# RGB_32x64_Shield_for_Arduino_Mega.net
KiCad netlist of a schematic drawn in EAGLE
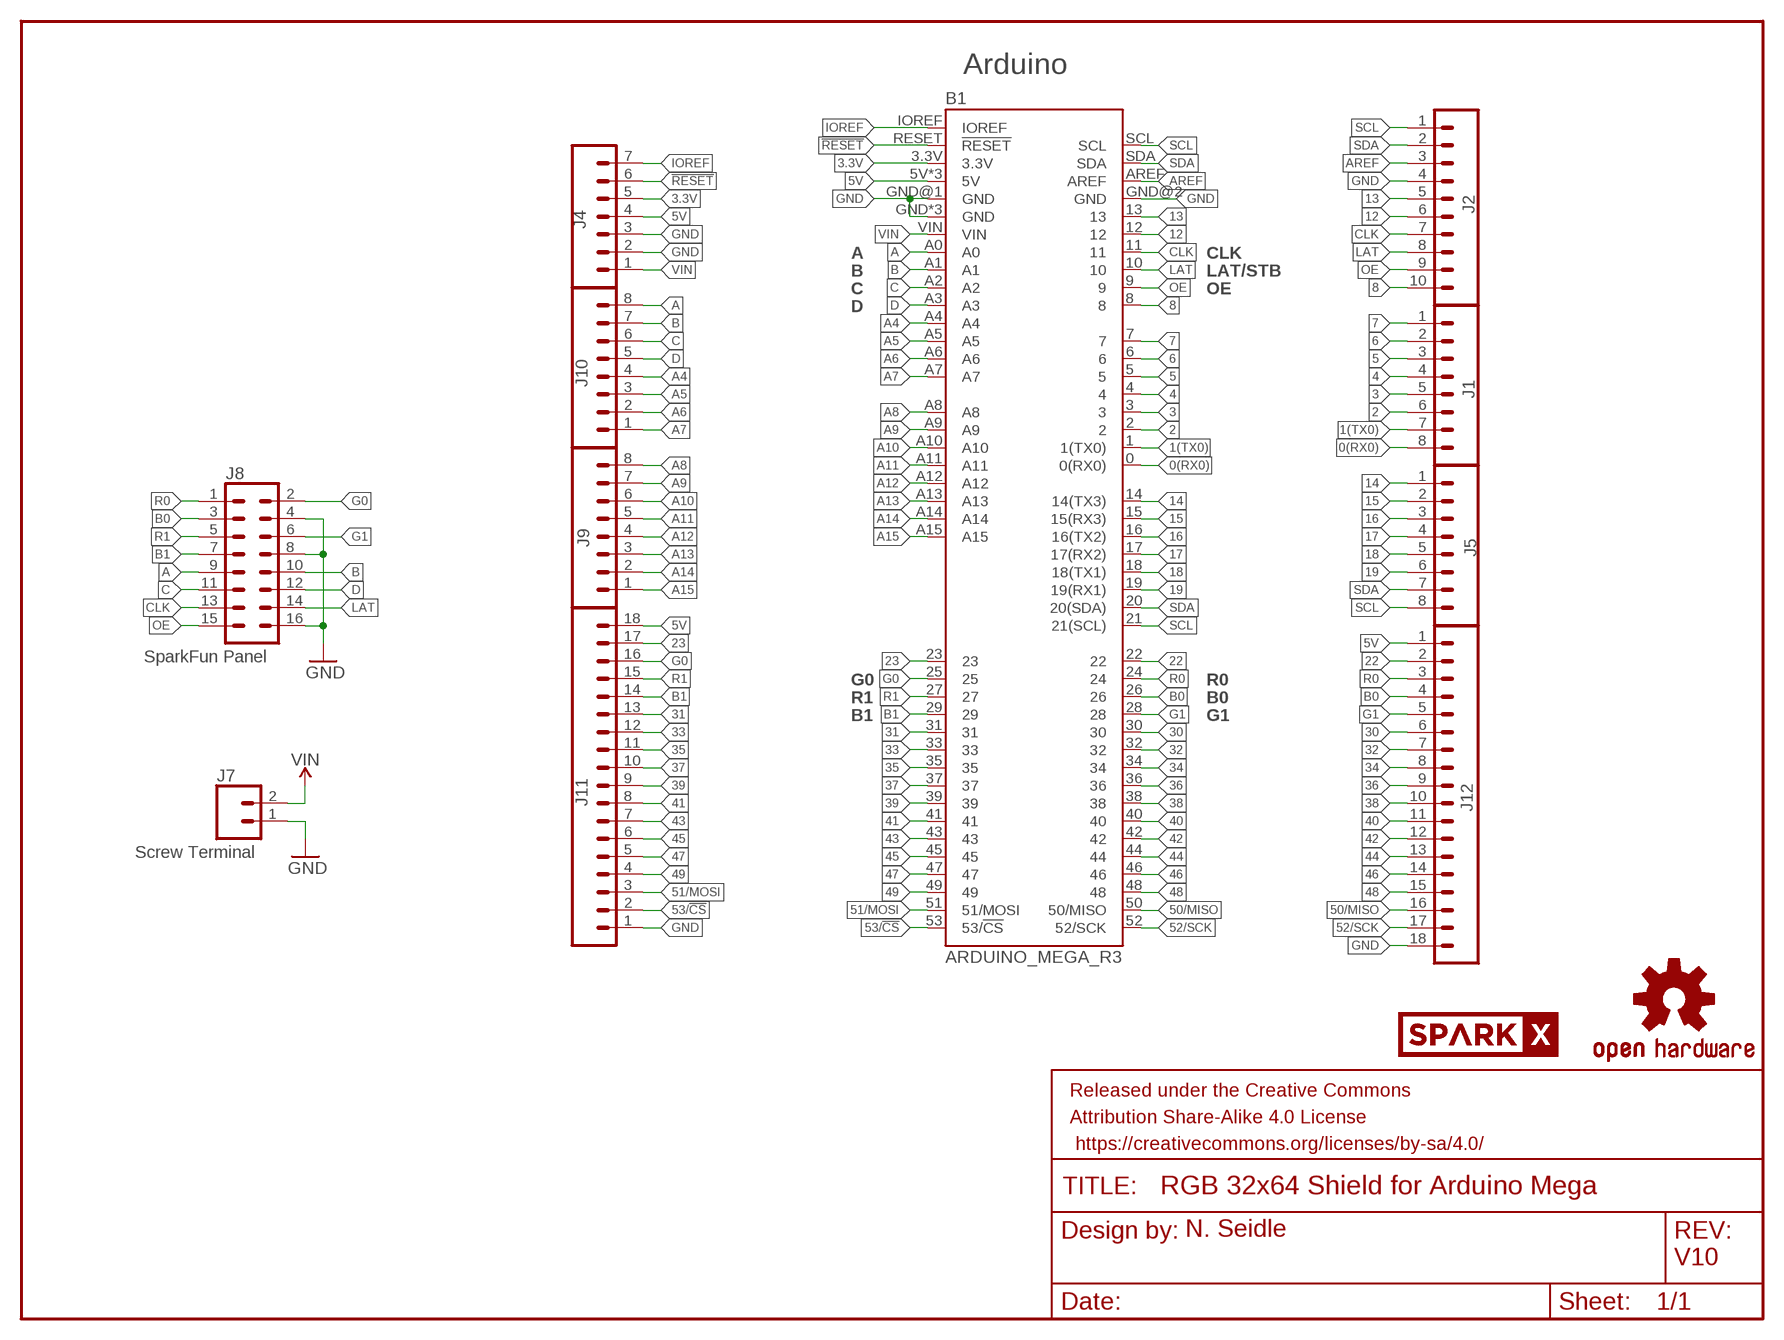
[diagram p0: schematic, sheet 1]

(export (version "E")
  (design (tool "Eeschema 10.0.6"))
  (components
    (comp (ref "B1")
      (value "ARDUINO_MEGA_R3")
      (footprint "eagle-import:ARDUINO_MEGA_NO_SILK")
      (libsource (lib "eagle-import") (part "ARDUINO_MEGA_R3FULL"))
    )
    (comp (ref "FRAME1")
      (value "FRAME-LETTER")
      (footprint "eagle-import:CREATIVE_COMMONS")
      (libsource (lib "eagle-import") (part "FRAME-LETTER"))
    )
    (comp (ref "J1")
      (value "CONN_08NO_SILK_FEMALE_PTH")
      (footprint "eagle-import:1X08_NO_SILK")
      (libsource (lib "eagle-import") (part "CONN_08NO_SILK_FEMALE_PTH"))
    )
    (comp (ref "J2")
      (value "CONN_10NO_SILK_PTH_FEMALE")
      (footprint "eagle-import:1X10_NO_SILK")
      (libsource (lib "eagle-import") (part "CONN_10NO_SILK_PTH_FEMALE"))
    )
    (comp (ref "J4")
      (value "CONN_07NO_SILK")
      (footprint "eagle-import:1X07_NO_SILK")
      (libsource (lib "eagle-import") (part "CONN_07NO_SILK"))
    )
    (comp (ref "J5")
      (value "CONN_08NO_SILK_FEMALE_PTH")
      (footprint "eagle-import:1X08_NO_SILK")
      (libsource (lib "eagle-import") (part "CONN_08NO_SILK_FEMALE_PTH"))
    )
    (comp (ref "J7")
      (value "Screw Terminal")
      (footprint "eagle-import:SCREWTERMINAL-5MM-2")
      (libsource (lib "eagle-import") (part "CONN_025MM"))
    )
    (comp (ref "J8")
      (value "SparkFun Panel")
      (footprint "eagle-import:2X8-SHROUDED_LOCK")
      (libsource (lib "eagle-import") (part "CONN_08X2_SHROUD"))
    )
    (comp (ref "J9")
      (value "CONN_08NO_SILK_FEMALE_PTH")
      (footprint "eagle-import:1X08_NO_SILK")
      (libsource (lib "eagle-import") (part "CONN_08NO_SILK_FEMALE_PTH"))
    )
    (comp (ref "J10")
      (value "CONN_08NO_SILK_FEMALE_PTH")
      (footprint "eagle-import:1X08_NO_SILK")
      (libsource (lib "eagle-import") (part "CONN_08NO_SILK_FEMALE_PTH"))
    )
    (comp (ref "J11")
      (value "CONN_18")
      (footprint "eagle-import:1X18_NO_SILK")
      (libsource (lib "eagle-import") (part "CONN_18"))
    )
    (comp (ref "J12")
      (value "CONN_18")
      (footprint "eagle-import:1X18_NO_SILK")
      (libsource (lib "eagle-import") (part "CONN_18"))
    )
    (comp (ref "LOGO1")
      (value "OSHW-LOGOMINI")
      (footprint "eagle-import:OSHW-LOGO-MINI")
      (libsource (lib "eagle-import") (part "OSHW-LOGOMINI"))
    )
    (comp (ref "U$91")
      (value "SPARKX-LOGO4")
      (footprint "eagle-import:SPARKX-MEDIUM")
      (libsource (lib "eagle-import") (part "SPARKX-LOGO4"))
    )
  )
  (nets
    (net (code "1") (name "/53{slash}~{CS}") (class "Default")
      (node (ref "B1") (pin "53") (pinfunction "53/~{CS}_53") (pintype "bidirectional"))
      (node (ref "J11") (pin "2") (pinfunction "2_2") (pintype "passive"))
    )
    (net (code "2") (name "/~{RESET}") (class "Default")
      (node (ref "B1") (pin "RESET") (pinfunction "~{RESET}_RESET") (pintype "bidirectional"))
      (node (ref "J4") (pin "6") (pinfunction "6_6") (pintype "passive"))
    )
    (net (code "3") (name "0(RX0)") (class "Default")
      (node (ref "B1") (pin "0") (pinfunction "0(RX0)_0") (pintype "bidirectional"))
      (node (ref "J1") (pin "8") (pinfunction "8_8") (pintype "passive"))
    )
    (net (code "4") (name "1(TX0)") (class "Default")
      (node (ref "B1") (pin "1") (pinfunction "1(TX0)_1") (pintype "bidirectional"))
      (node (ref "J1") (pin "7") (pinfunction "7_7") (pintype "passive"))
    )
    (net (code "5") (name "2") (class "Default")
      (node (ref "B1") (pin "2") (pinfunction "2_2") (pintype "bidirectional"))
      (node (ref "J1") (pin "6") (pinfunction "6_6") (pintype "passive"))
    )
    (net (code "6") (name "3") (class "Default")
      (node (ref "B1") (pin "3") (pinfunction "3_3") (pintype "bidirectional"))
      (node (ref "J1") (pin "5") (pinfunction "5_5") (pintype "passive"))
    )
    (net (code "7") (name "3.3V") (class "Default")
      (node (ref "B1") (pin "3.3V") (pinfunction "3.3V_3.3V") (pintype "bidirectional"))
      (node (ref "J4") (pin "5") (pinfunction "5_5") (pintype "passive"))
    )
    (net (code "8") (name "4") (class "Default")
      (node (ref "B1") (pin "4") (pinfunction "4_4") (pintype "bidirectional"))
      (node (ref "J1") (pin "4") (pinfunction "4_4") (pintype "passive"))
    )
    (net (code "9") (name "5") (class "Default")
      (node (ref "B1") (pin "5") (pinfunction "5_5") (pintype "bidirectional"))
      (node (ref "J1") (pin "3") (pinfunction "3_3") (pintype "passive"))
    )
    (net (code "10") (name "5V") (class "Default")
      (node (ref "B1") (pin "5V") (pinfunction "5V_5V") (pintype "bidirectional"))
      (node (ref "B1") (pin "5V@1") (pinfunction "5V_5V@1") (pintype "bidirectional"))
      (node (ref "B1") (pin "5V@2") (pinfunction "5V_5V@2") (pintype "bidirectional"))
      (node (ref "J11") (pin "18") (pinfunction "18_18") (pintype "passive"))
      (node (ref "J12") (pin "1") (pinfunction "1_1") (pintype "passive"))
      (node (ref "J4") (pin "4") (pinfunction "4_4") (pintype "passive"))
    )
    (net (code "11") (name "6") (class "Default")
      (node (ref "B1") (pin "6") (pinfunction "6_6") (pintype "bidirectional"))
      (node (ref "J1") (pin "2") (pinfunction "2_2") (pintype "passive"))
    )
    (net (code "12") (name "7") (class "Default")
      (node (ref "B1") (pin "7") (pinfunction "7_7") (pintype "bidirectional"))
      (node (ref "J1") (pin "1") (pinfunction "1_1") (pintype "passive"))
    )
    (net (code "13") (name "8") (class "Default")
      (node (ref "B1") (pin "8") (pinfunction "8_8") (pintype "bidirectional"))
      (node (ref "J2") (pin "10") (pinfunction "10_10") (pintype "passive"))
    )
    (net (code "14") (name "12") (class "Default")
      (node (ref "B1") (pin "12") (pinfunction "12_12") (pintype "bidirectional"))
      (node (ref "J2") (pin "6") (pinfunction "6_6") (pintype "passive"))
    )
    (net (code "15") (name "13") (class "Default")
      (node (ref "B1") (pin "13") (pinfunction "13_13") (pintype "bidirectional"))
      (node (ref "J2") (pin "5") (pinfunction "5_5") (pintype "passive"))
    )
    (net (code "16") (name "14") (class "Default")
      (node (ref "B1") (pin "14") (pinfunction "14(TX3)_14") (pintype "bidirectional"))
      (node (ref "J5") (pin "1") (pinfunction "1_1") (pintype "passive"))
    )
    (net (code "17") (name "15") (class "Default")
      (node (ref "B1") (pin "15") (pinfunction "15(RX3)_15") (pintype "bidirectional"))
      (node (ref "J5") (pin "2") (pinfunction "2_2") (pintype "passive"))
    )
    (net (code "18") (name "16") (class "Default")
      (node (ref "B1") (pin "16") (pinfunction "16(TX2)_16") (pintype "bidirectional"))
      (node (ref "J5") (pin "3") (pinfunction "3_3") (pintype "passive"))
    )
    (net (code "19") (name "17") (class "Default")
      (node (ref "B1") (pin "17") (pinfunction "17(RX2)_17") (pintype "bidirectional"))
      (node (ref "J5") (pin "4") (pinfunction "4_4") (pintype "passive"))
    )
    (net (code "20") (name "18") (class "Default")
      (node (ref "B1") (pin "18") (pinfunction "18(TX1)_18") (pintype "bidirectional"))
      (node (ref "J5") (pin "5") (pinfunction "5_5") (pintype "passive"))
    )
    (net (code "21") (name "19") (class "Default")
      (node (ref "B1") (pin "19") (pinfunction "19(RX1)_19") (pintype "bidirectional"))
      (node (ref "J5") (pin "6") (pinfunction "6_6") (pintype "passive"))
    )
    (net (code "22") (name "22") (class "Default")
      (node (ref "B1") (pin "22") (pinfunction "22_22") (pintype "bidirectional"))
      (node (ref "J12") (pin "2") (pinfunction "2_2") (pintype "passive"))
    )
    (net (code "23") (name "23") (class "Default")
      (node (ref "B1") (pin "23") (pinfunction "23_23") (pintype "bidirectional"))
      (node (ref "J11") (pin "17") (pinfunction "17_17") (pintype "passive"))
    )
    (net (code "24") (name "30") (class "Default")
      (node (ref "B1") (pin "30") (pinfunction "30_30") (pintype "bidirectional"))
      (node (ref "J12") (pin "6") (pinfunction "6_6") (pintype "passive"))
    )
    (net (code "25") (name "31") (class "Default")
      (node (ref "B1") (pin "31") (pinfunction "31_31") (pintype "bidirectional"))
      (node (ref "J11") (pin "13") (pinfunction "13_13") (pintype "passive"))
    )
    (net (code "26") (name "32") (class "Default")
      (node (ref "B1") (pin "32") (pinfunction "32_32") (pintype "bidirectional"))
      (node (ref "J12") (pin "7") (pinfunction "7_7") (pintype "passive"))
    )
    (net (code "27") (name "33") (class "Default")
      (node (ref "B1") (pin "33") (pinfunction "33_33") (pintype "bidirectional"))
      (node (ref "J11") (pin "12") (pinfunction "12_12") (pintype "passive"))
    )
    (net (code "28") (name "34") (class "Default")
      (node (ref "B1") (pin "34") (pinfunction "34_34") (pintype "bidirectional"))
      (node (ref "J12") (pin "8") (pinfunction "8_8") (pintype "passive"))
    )
    (net (code "29") (name "35") (class "Default")
      (node (ref "B1") (pin "35") (pinfunction "35_35") (pintype "bidirectional"))
      (node (ref "J11") (pin "11") (pinfunction "11_11") (pintype "passive"))
    )
    (net (code "30") (name "36") (class "Default")
      (node (ref "B1") (pin "36") (pinfunction "36_36") (pintype "bidirectional"))
      (node (ref "J12") (pin "9") (pinfunction "9_9") (pintype "passive"))
    )
    (net (code "31") (name "37") (class "Default")
      (node (ref "B1") (pin "37") (pinfunction "37_37") (pintype "bidirectional"))
      (node (ref "J11") (pin "10") (pinfunction "10_10") (pintype "passive"))
    )
    (net (code "32") (name "38") (class "Default")
      (node (ref "B1") (pin "38") (pinfunction "38_38") (pintype "bidirectional"))
      (node (ref "J12") (pin "10") (pinfunction "10_10") (pintype "passive"))
    )
    (net (code "33") (name "39") (class "Default")
      (node (ref "B1") (pin "39") (pinfunction "39_39") (pintype "bidirectional"))
      (node (ref "J11") (pin "9") (pinfunction "9_9") (pintype "passive"))
    )
    (net (code "34") (name "40") (class "Default")
      (node (ref "B1") (pin "40") (pinfunction "40_40") (pintype "bidirectional"))
      (node (ref "J12") (pin "11") (pinfunction "11_11") (pintype "passive"))
    )
    (net (code "35") (name "41") (class "Default")
      (node (ref "B1") (pin "41") (pinfunction "41_41") (pintype "bidirectional"))
      (node (ref "J11") (pin "8") (pinfunction "8_8") (pintype "passive"))
    )
    (net (code "36") (name "42") (class "Default")
      (node (ref "B1") (pin "42") (pinfunction "42_42") (pintype "bidirectional"))
      (node (ref "J12") (pin "12") (pinfunction "12_12") (pintype "passive"))
    )
    (net (code "37") (name "43") (class "Default")
      (node (ref "B1") (pin "43") (pinfunction "43_43") (pintype "bidirectional"))
      (node (ref "J11") (pin "7") (pinfunction "7_7") (pintype "passive"))
    )
    (net (code "38") (name "44") (class "Default")
      (node (ref "B1") (pin "44") (pinfunction "44_44") (pintype "bidirectional"))
      (node (ref "J12") (pin "13") (pinfunction "13_13") (pintype "passive"))
    )
    (net (code "39") (name "45") (class "Default")
      (node (ref "B1") (pin "45") (pinfunction "45_45") (pintype "bidirectional"))
      (node (ref "J11") (pin "6") (pinfunction "6_6") (pintype "passive"))
    )
    (net (code "40") (name "46") (class "Default")
      (node (ref "B1") (pin "46") (pinfunction "46_46") (pintype "bidirectional"))
      (node (ref "J12") (pin "14") (pinfunction "14_14") (pintype "passive"))
    )
    (net (code "41") (name "47") (class "Default")
      (node (ref "B1") (pin "47") (pinfunction "47_47") (pintype "bidirectional"))
      (node (ref "J11") (pin "5") (pinfunction "5_5") (pintype "passive"))
    )
    (net (code "42") (name "48") (class "Default")
      (node (ref "B1") (pin "48") (pinfunction "48_48") (pintype "bidirectional"))
      (node (ref "J12") (pin "15") (pinfunction "15_15") (pintype "passive"))
    )
    (net (code "43") (name "49") (class "Default")
      (node (ref "B1") (pin "49") (pinfunction "49_49") (pintype "bidirectional"))
      (node (ref "J11") (pin "4") (pinfunction "4_4") (pintype "passive"))
    )
    (net (code "44") (name "50{slash}MISO") (class "Default")
      (node (ref "B1") (pin "50") (pinfunction "50/MISO_50") (pintype "bidirectional"))
      (node (ref "J12") (pin "16") (pinfunction "16_16") (pintype "passive"))
    )
    (net (code "45") (name "51{slash}MOSI") (class "Default")
      (node (ref "B1") (pin "51") (pinfunction "51/MOSI_51") (pintype "bidirectional"))
      (node (ref "J11") (pin "3") (pinfunction "3_3") (pintype "passive"))
    )
    (net (code "46") (name "52{slash}SCK") (class "Default")
      (node (ref "B1") (pin "52") (pinfunction "52/SCK_52") (pintype "bidirectional"))
      (node (ref "J12") (pin "17") (pinfunction "17_17") (pintype "passive"))
    )
    (net (code "47") (name "A") (class "Default")
      (node (ref "B1") (pin "A0") (pinfunction "A0_A0") (pintype "bidirectional"))
      (node (ref "J10") (pin "8") (pinfunction "8_8") (pintype "passive"))
      (node (ref "J8") (pin "9") (pinfunction "9_9") (pintype "passive"))
    )
    (net (code "48") (name "A4") (class "Default")
      (node (ref "B1") (pin "A4") (pinfunction "A4_A4") (pintype "bidirectional"))
      (node (ref "J10") (pin "4") (pinfunction "4_4") (pintype "passive"))
    )
    (net (code "49") (name "A5") (class "Default")
      (node (ref "B1") (pin "A5") (pinfunction "A5_A5") (pintype "bidirectional"))
      (node (ref "J10") (pin "3") (pinfunction "3_3") (pintype "passive"))
    )
    (net (code "50") (name "A6") (class "Default")
      (node (ref "B1") (pin "A6") (pinfunction "A6_A6") (pintype "bidirectional"))
      (node (ref "J10") (pin "2") (pinfunction "2_2") (pintype "passive"))
    )
    (net (code "51") (name "A7") (class "Default")
      (node (ref "B1") (pin "A7") (pinfunction "A7_A7") (pintype "bidirectional"))
      (node (ref "J10") (pin "1") (pinfunction "1_1") (pintype "passive"))
    )
    (net (code "52") (name "A8") (class "Default")
      (node (ref "B1") (pin "A8") (pinfunction "A8_A8") (pintype "bidirectional"))
      (node (ref "J9") (pin "8") (pinfunction "8_8") (pintype "passive"))
    )
    (net (code "53") (name "A9") (class "Default")
      (node (ref "B1") (pin "A9") (pinfunction "A9_A9") (pintype "bidirectional"))
      (node (ref "J9") (pin "7") (pinfunction "7_7") (pintype "passive"))
    )
    (net (code "54") (name "A10") (class "Default")
      (node (ref "B1") (pin "A10") (pinfunction "A10_A10") (pintype "bidirectional"))
      (node (ref "J9") (pin "6") (pinfunction "6_6") (pintype "passive"))
    )
    (net (code "55") (name "A11") (class "Default")
      (node (ref "B1") (pin "A11") (pinfunction "A11_A11") (pintype "bidirectional"))
      (node (ref "J9") (pin "5") (pinfunction "5_5") (pintype "passive"))
    )
    (net (code "56") (name "A12") (class "Default")
      (node (ref "B1") (pin "A12") (pinfunction "A12_A12") (pintype "bidirectional"))
      (node (ref "J9") (pin "4") (pinfunction "4_4") (pintype "passive"))
    )
    (net (code "57") (name "A13") (class "Default")
      (node (ref "B1") (pin "A13") (pinfunction "A13_A13") (pintype "bidirectional"))
      (node (ref "J9") (pin "3") (pinfunction "3_3") (pintype "passive"))
    )
    (net (code "58") (name "A14") (class "Default")
      (node (ref "B1") (pin "A14") (pinfunction "A14_A14") (pintype "bidirectional"))
      (node (ref "J9") (pin "2") (pinfunction "2_2") (pintype "passive"))
    )
    (net (code "59") (name "A15") (class "Default")
      (node (ref "B1") (pin "A15") (pinfunction "A15_A15") (pintype "bidirectional"))
      (node (ref "J9") (pin "1") (pinfunction "1_1") (pintype "passive"))
    )
    (net (code "60") (name "AREF") (class "Default")
      (node (ref "B1") (pin "AREF") (pinfunction "AREF_AREF") (pintype "bidirectional"))
      (node (ref "J2") (pin "3") (pinfunction "3_3") (pintype "passive"))
    )
    (net (code "61") (name "B") (class "Default")
      (node (ref "B1") (pin "A1") (pinfunction "A1_A1") (pintype "bidirectional"))
      (node (ref "J10") (pin "7") (pinfunction "7_7") (pintype "passive"))
      (node (ref "J8") (pin "10") (pinfunction "10_10") (pintype "passive"))
    )
    (net (code "62") (name "B0") (class "Default")
      (node (ref "B1") (pin "26") (pinfunction "26_26") (pintype "bidirectional"))
      (node (ref "J12") (pin "4") (pinfunction "4_4") (pintype "passive"))
      (node (ref "J8") (pin "3") (pinfunction "3_3") (pintype "passive"))
    )
    (net (code "63") (name "B1") (class "Default")
      (node (ref "B1") (pin "29") (pinfunction "29_29") (pintype "bidirectional"))
      (node (ref "J11") (pin "14") (pinfunction "14_14") (pintype "passive"))
      (node (ref "J8") (pin "7") (pinfunction "7_7") (pintype "passive"))
    )
    (net (code "64") (name "C") (class "Default")
      (node (ref "B1") (pin "A2") (pinfunction "A2_A2") (pintype "bidirectional"))
      (node (ref "J10") (pin "6") (pinfunction "6_6") (pintype "passive"))
      (node (ref "J8") (pin "11") (pinfunction "11_11") (pintype "passive"))
    )
    (net (code "65") (name "CLK") (class "Default")
      (node (ref "B1") (pin "11") (pinfunction "11_11") (pintype "bidirectional"))
      (node (ref "J2") (pin "7") (pinfunction "7_7") (pintype "passive"))
      (node (ref "J8") (pin "13") (pinfunction "13_13") (pintype "passive"))
    )
    (net (code "66") (name "D") (class "Default")
      (node (ref "B1") (pin "A3") (pinfunction "A3_A3") (pintype "bidirectional"))
      (node (ref "J10") (pin "5") (pinfunction "5_5") (pintype "passive"))
      (node (ref "J8") (pin "12") (pinfunction "12_12") (pintype "passive"))
    )
    (net (code "67") (name "G0") (class "Default")
      (node (ref "B1") (pin "25") (pinfunction "25_25") (pintype "bidirectional"))
      (node (ref "J11") (pin "16") (pinfunction "16_16") (pintype "passive"))
      (node (ref "J8") (pin "2") (pinfunction "2_2") (pintype "passive"))
    )
    (net (code "68") (name "G1") (class "Default")
      (node (ref "B1") (pin "28") (pinfunction "28_28") (pintype "bidirectional"))
      (node (ref "J12") (pin "5") (pinfunction "5_5") (pintype "passive"))
      (node (ref "J8") (pin "6") (pinfunction "6_6") (pintype "passive"))
    )
    (net (code "69") (name "GND") (class "Default")
      (node (ref "B1") (pin "GND") (pinfunction "GND_GND") (pintype "bidirectional"))
      (node (ref "B1") (pin "GND@1") (pinfunction "GND_GND@1") (pintype "bidirectional"))
      (node (ref "B1") (pin "GND@2") (pinfunction "GND_GND@2") (pintype "bidirectional"))
      (node (ref "B1") (pin "GND@3") (pinfunction "GND_GND@3") (pintype "bidirectional"))
      (node (ref "B1") (pin "GND@4") (pinfunction "GND_GND@4") (pintype "bidirectional"))
      (node (ref "J11") (pin "1") (pinfunction "1_1") (pintype "passive"))
      (node (ref "J12") (pin "18") (pinfunction "18_18") (pintype "passive"))
      (node (ref "J2") (pin "4") (pinfunction "4_4") (pintype "passive"))
      (node (ref "J4") (pin "2") (pinfunction "2_2") (pintype "passive"))
      (node (ref "J4") (pin "3") (pinfunction "3_3") (pintype "passive"))
      (node (ref "J7") (pin "1") (pinfunction "1_1") (pintype "passive"))
      (node (ref "J8") (pin "16") (pinfunction "16_16") (pintype "passive"))
      (node (ref "J8") (pin "4") (pinfunction "4_4") (pintype "passive"))
      (node (ref "J8") (pin "8") (pinfunction "8_8") (pintype "passive"))
    )
    (net (code "70") (name "IOREF") (class "Default")
      (node (ref "B1") (pin "IOREF") (pinfunction "IOREF_IOREF") (pintype "bidirectional"))
      (node (ref "J4") (pin "7") (pinfunction "7_7") (pintype "passive"))
    )
    (net (code "71") (name "LAT") (class "Default")
      (node (ref "B1") (pin "10") (pinfunction "10_10") (pintype "bidirectional"))
      (node (ref "J2") (pin "8") (pinfunction "8_8") (pintype "passive"))
      (node (ref "J8") (pin "14") (pinfunction "14_14") (pintype "passive"))
    )
    (net (code "72") (name "OE") (class "Default")
      (node (ref "B1") (pin "9") (pinfunction "9_9") (pintype "bidirectional"))
      (node (ref "J2") (pin "9") (pinfunction "9_9") (pintype "passive"))
      (node (ref "J8") (pin "15") (pinfunction "15_15") (pintype "passive"))
    )
    (net (code "73") (name "R0") (class "Default")
      (node (ref "B1") (pin "24") (pinfunction "24_24") (pintype "bidirectional"))
      (node (ref "J12") (pin "3") (pinfunction "3_3") (pintype "passive"))
      (node (ref "J8") (pin "1") (pinfunction "1_1") (pintype "passive"))
    )
    (net (code "74") (name "R1") (class "Default")
      (node (ref "B1") (pin "27") (pinfunction "27_27") (pintype "bidirectional"))
      (node (ref "J11") (pin "15") (pinfunction "15_15") (pintype "passive"))
      (node (ref "J8") (pin "5") (pinfunction "5_5") (pintype "passive"))
    )
    (net (code "75") (name "SCL") (class "Default")
      (node (ref "B1") (pin "21") (pinfunction "21(SCL)_21") (pintype "bidirectional"))
      (node (ref "B1") (pin "SCL") (pinfunction "SCL_SCL") (pintype "bidirectional"))
      (node (ref "J2") (pin "1") (pinfunction "1_1") (pintype "passive"))
      (node (ref "J5") (pin "8") (pinfunction "8_8") (pintype "passive"))
    )
    (net (code "76") (name "SDA") (class "Default")
      (node (ref "B1") (pin "20") (pinfunction "20(SDA)_20") (pintype "bidirectional"))
      (node (ref "B1") (pin "SDA") (pinfunction "SDA_SDA") (pintype "bidirectional"))
      (node (ref "J2") (pin "2") (pinfunction "2_2") (pintype "passive"))
      (node (ref "J5") (pin "7") (pinfunction "7_7") (pintype "passive"))
    )
    (net (code "77") (name "VIN") (class "Default")
      (node (ref "B1") (pin "VIN") (pinfunction "VIN_VIN") (pintype "bidirectional"))
      (node (ref "J4") (pin "1") (pinfunction "1_1") (pintype "passive"))
      (node (ref "J7") (pin "2") (pinfunction "2_2") (pintype "passive"))
    )
  )
)
